# Main_NTC_Extension_6Fach.net
KiCad netlist of a schematic drawn in Altium Designer
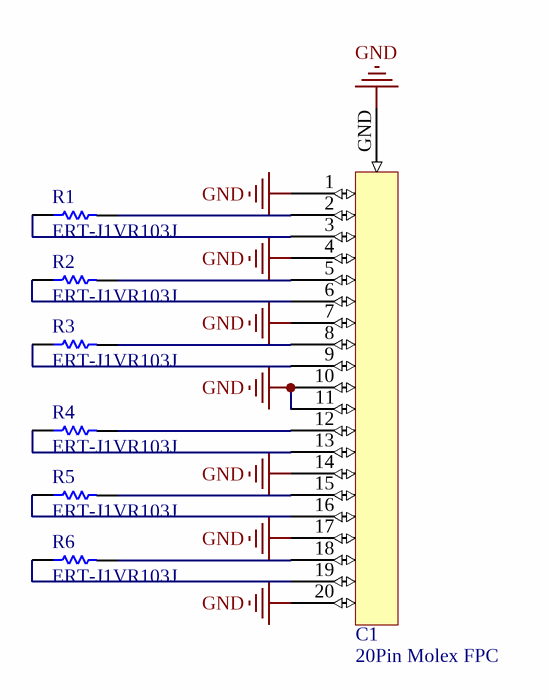
[diagram p0: Main_NTC_Extension_6Fach.SchDoc]

(export (version "E")
  (design (tool "Eeschema 10.0.6"))
  (components
    (comp (ref "C1")
      (value "20Pin Molex FPC")
      (footprint "Molex 20 Pin FPC")
      (description "Flex PCB part for the Molex 20pin FCC")
      (libsource (lib "Integrated_LibraryLukas_New") (part "20Pin Molex FPC"))
    )
    (comp (ref "R1")
      (value "ERT-J1VR103J")
      (footprint "RESC1608X90X30ML15T20")
      (fields (field (name "MANUFACTURER") "Panasonic"))
      (libsource (lib "Altium Content Vault") (part "RES"))
    )
    (comp (ref "R2")
      (value "ERT-J1VR103J")
      (footprint "RESC1608X90X30ML15T20")
      (fields (field (name "MANUFACTURER") "Panasonic"))
      (libsource (lib "Altium Content Vault") (part "RES"))
    )
    (comp (ref "R3")
      (value "ERT-J1VR103J")
      (footprint "RESC1608X90X30ML15T20")
      (fields (field (name "MANUFACTURER") "Panasonic"))
      (libsource (lib "Altium Content Vault") (part "RES"))
    )
    (comp (ref "R4")
      (value "ERT-J1VR103J")
      (footprint "RESC1608X90X30ML15T20")
      (fields (field (name "MANUFACTURER") "Panasonic"))
      (libsource (lib "Altium Content Vault") (part "RES"))
    )
    (comp (ref "R5")
      (value "ERT-J1VR103J")
      (footprint "RESC1608X90X30ML15T20")
      (fields (field (name "MANUFACTURER") "Panasonic"))
      (libsource (lib "Altium Content Vault") (part "RES"))
    )
    (comp (ref "R6")
      (value "ERT-J1VR103J")
      (footprint "RESC1608X90X30ML15T20")
      (fields (field (name "MANUFACTURER") "Panasonic"))
      (libsource (lib "Altium Content Vault") (part "RES"))
    )
  )
  (nets
    (net (code "1") (name "GND") (class "Default")
      (node (ref "C1") (pin "1") (pintype "bidirectional"))
      (node (ref "C1") (pin "10") (pintype "bidirectional"))
      (node (ref "C1") (pin "11") (pintype "bidirectional"))
      (node (ref "C1") (pin "14") (pintype "bidirectional"))
      (node (ref "C1") (pin "17") (pintype "bidirectional"))
      (node (ref "C1") (pin "20") (pintype "bidirectional"))
      (node (ref "C1") (pin "4") (pintype "bidirectional"))
      (node (ref "C1") (pin "7") (pintype "bidirectional"))
      (node (ref "C1") (pin "GND") (pintype "input"))
    )
    (net (code "2") (name "Net-(C1-Pad2)") (class "Default")
      (node (ref "C1") (pin "2") (pintype "bidirectional"))
      (node (ref "R1") (pin "2") (pinfunction "2_2") (pintype "passive"))
    )
    (net (code "3") (name "Net-(C1-Pad3)") (class "Default")
      (node (ref "C1") (pin "3") (pintype "bidirectional"))
      (node (ref "R1") (pin "1") (pinfunction "1_1") (pintype "passive"))
    )
    (net (code "4") (name "Net-(C1-Pad5)") (class "Default")
      (node (ref "C1") (pin "5") (pintype "bidirectional"))
      (node (ref "R2") (pin "2") (pinfunction "2_2") (pintype "passive"))
    )
    (net (code "5") (name "Net-(C1-Pad6)") (class "Default")
      (node (ref "C1") (pin "6") (pintype "bidirectional"))
      (node (ref "R2") (pin "1") (pinfunction "1_1") (pintype "passive"))
    )
    (net (code "6") (name "Net-(C1-Pad8)") (class "Default")
      (node (ref "C1") (pin "8") (pintype "bidirectional"))
      (node (ref "R3") (pin "2") (pinfunction "2_2") (pintype "passive"))
    )
    (net (code "7") (name "Net-(C1-Pad9)") (class "Default")
      (node (ref "C1") (pin "9") (pintype "bidirectional"))
      (node (ref "R3") (pin "1") (pinfunction "1_1") (pintype "passive"))
    )
    (net (code "8") (name "Net-(C1-Pad12)") (class "Default")
      (node (ref "C1") (pin "12") (pintype "bidirectional"))
      (node (ref "R4") (pin "2") (pinfunction "2_2") (pintype "passive"))
    )
    (net (code "9") (name "Net-(C1-Pad13)") (class "Default")
      (node (ref "C1") (pin "13") (pintype "bidirectional"))
      (node (ref "R4") (pin "1") (pinfunction "1_1") (pintype "passive"))
    )
    (net (code "10") (name "Net-(C1-Pad15)") (class "Default")
      (node (ref "C1") (pin "15") (pintype "bidirectional"))
      (node (ref "R5") (pin "2") (pinfunction "2_2") (pintype "passive"))
    )
    (net (code "11") (name "Net-(C1-Pad16)") (class "Default")
      (node (ref "C1") (pin "16") (pintype "bidirectional"))
      (node (ref "R5") (pin "1") (pinfunction "1_1") (pintype "passive"))
    )
    (net (code "12") (name "Net-(C1-Pad18)") (class "Default")
      (node (ref "C1") (pin "18") (pintype "bidirectional"))
      (node (ref "R6") (pin "2") (pinfunction "2_2") (pintype "passive"))
    )
    (net (code "13") (name "Net-(C1-Pad19)") (class "Default")
      (node (ref "C1") (pin "19") (pintype "bidirectional"))
      (node (ref "R6") (pin "1") (pinfunction "1_1") (pintype "passive"))
    )
  )
)
